# dwm1000_ff3_brd.net
KiCad netlist of a schematic drawn in EAGLE
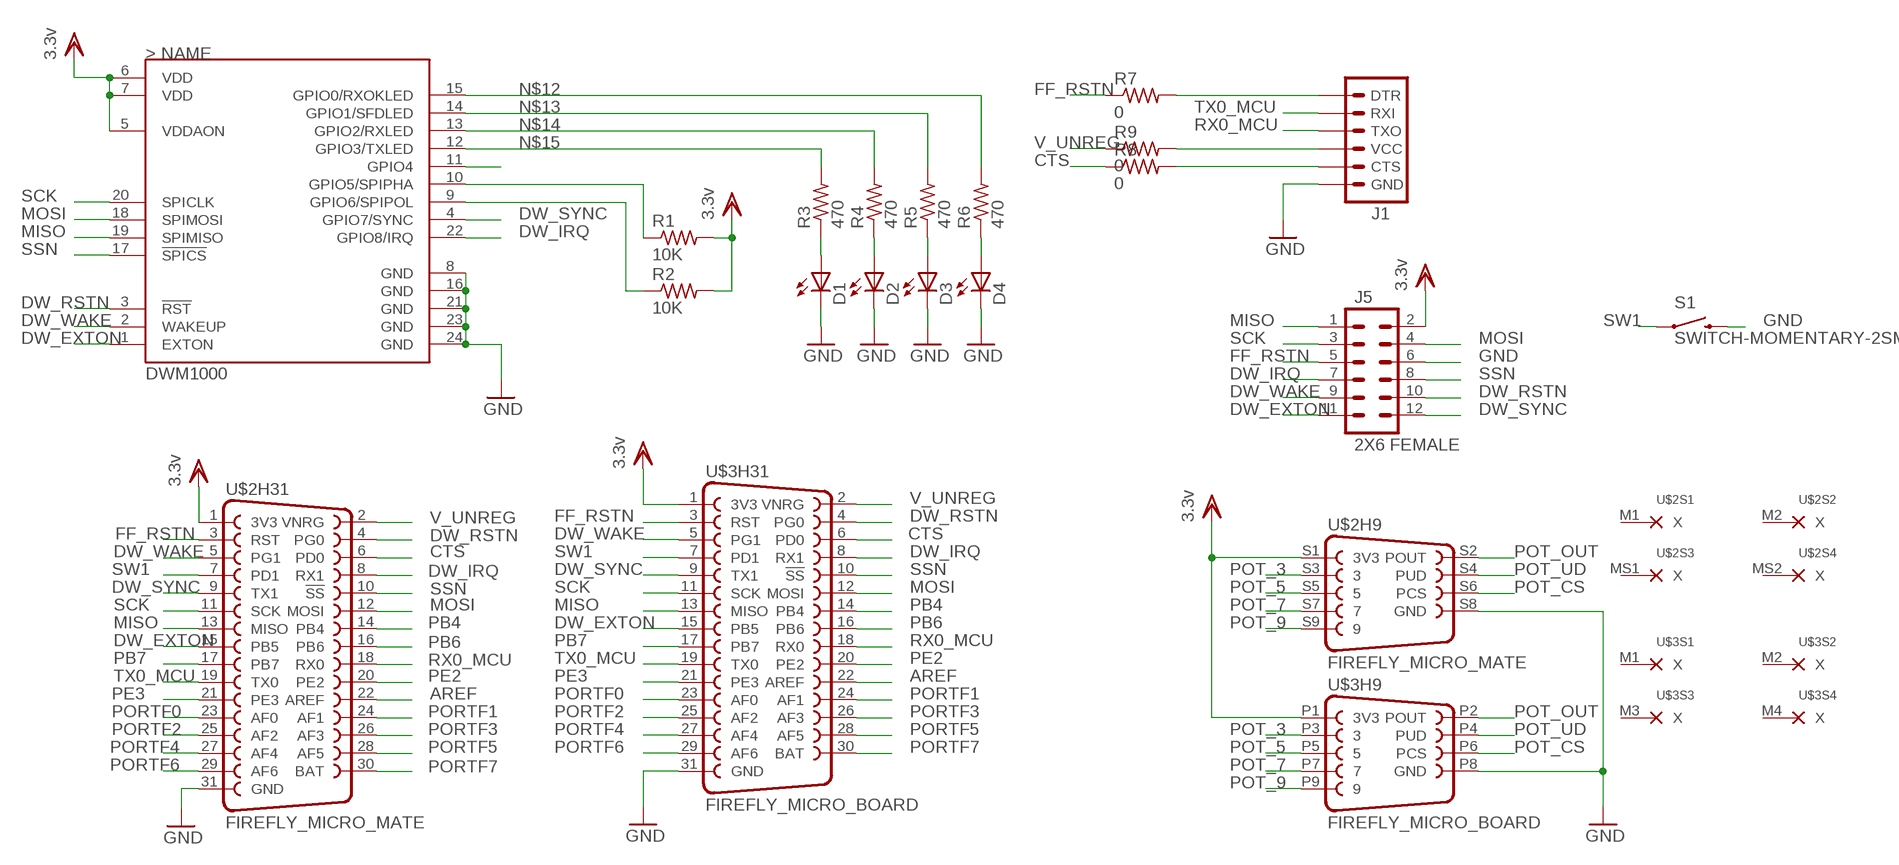
[diagram p0: schematic, sheet 1]

(export (version "E")
  (design (tool "Eeschema 10.0.6"))
  (components
    (comp (ref "D1")
      (value "LEDCHIP-LED0603")
      (footprint "eagle-import:CHIP-LED0603")
      (libsource (lib "eagle-import") (part "LEDCHIP-LED0603"))
    )
    (comp (ref "D2")
      (value "LEDCHIP-LED0603")
      (footprint "eagle-import:CHIP-LED0603")
      (libsource (lib "eagle-import") (part "LEDCHIP-LED0603"))
    )
    (comp (ref "D3")
      (value "LEDCHIP-LED0603")
      (footprint "eagle-import:CHIP-LED0603")
      (libsource (lib "eagle-import") (part "LEDCHIP-LED0603"))
    )
    (comp (ref "D4")
      (value "LEDCHIP-LED0603")
      (footprint "eagle-import:CHIP-LED0603")
      (libsource (lib "eagle-import") (part "LEDCHIP-LED0603"))
    )
    (comp (ref "J1")
      (value "ARDUINO_SERIAL_PROGRAMPTH")
      (footprint "eagle-import:1X06")
      (libsource (lib "eagle-import") (part "ARDUINO_SERIAL_PROGRAMPTH"))
    )
    (comp (ref "J5")
      (value "2X6 FEMALE")
      (footprint "eagle-import:2X6")
      (libsource (lib "eagle-import") (part "M06X2PTH_FEMALE"))
    )
    (comp (ref "R1")
      (value "10K")
      (footprint "eagle-import:R0603")
      (libsource (lib "eagle-import") (part "R-US_R0603"))
    )
    (comp (ref "R2")
      (value "10K")
      (footprint "eagle-import:R0603")
      (libsource (lib "eagle-import") (part "R-US_R0603"))
    )
    (comp (ref "R3")
      (value "470")
      (footprint "eagle-import:R0603")
      (libsource (lib "eagle-import") (part "R-US_R0603"))
    )
    (comp (ref "R4")
      (value "470")
      (footprint "eagle-import:R0603")
      (libsource (lib "eagle-import") (part "R-US_R0603"))
    )
    (comp (ref "R5")
      (value "470")
      (footprint "eagle-import:R0603")
      (libsource (lib "eagle-import") (part "R-US_R0603"))
    )
    (comp (ref "R6")
      (value "470")
      (footprint "eagle-import:R0603")
      (libsource (lib "eagle-import") (part "R-US_R0603"))
    )
    (comp (ref "R7")
      (value "0")
      (footprint "eagle-import:R0603")
      (libsource (lib "eagle-import") (part "R-US_R0603"))
    )
    (comp (ref "R8")
      (value "0")
      (footprint "eagle-import:R0603")
      (libsource (lib "eagle-import") (part "R-US_R0603"))
    )
    (comp (ref "R9")
      (value "0")
      (footprint "eagle-import:R0603")
      (libsource (lib "eagle-import") (part "R-US_R0603"))
    )
    (comp (ref "S1")
      (value "SWITCH-MOMENTARY-2SMD")
      (footprint "eagle-import:TACTILE-SWITCH-SMD")
      (libsource (lib "eagle-import") (part "SWITCH-MOMENTARY-2SMD"))
    )
    (comp (ref "U$1")
      (value "DWM1000")
      (footprint "eagle-import:DWM1000")
      (libsource (lib "eagle-import") (part "DWM1000"))
    )
    (comp (ref "U$2")
      (value "FIREFLY_MICRO_MATE")
      (footprint "eagle-import:FIREFLY_MICRO_MATE")
      (libsource (lib "eagle-import") (part "FIREFLY_MICRO_MATE"))
    )
    (comp (ref "U$3")
      (value "FIREFLY_MICRO_BOARD")
      (footprint "eagle-import:FIREFLY_MICRO_BOARD")
      (libsource (lib "eagle-import") (part "FIREFLY_MICRO_BOARD"))
    )
  )
  (nets
    (net (code "1") (name "/AREF") (class "Default")
      (node (ref "U$2") (pin "22") (pinfunction "AREF_22") (pintype "input"))
      (node (ref "U$3") (pin "22") (pinfunction "AREF_22") (pintype "input"))
    )
    (net (code "2") (name "/CTS") (class "Default")
      (node (ref "R8") (pin "1") (pinfunction "1_1") (pintype "passive"))
      (node (ref "U$2") (pin "6") (pinfunction "PD0_6") (pintype "bidirectional"))
      (node (ref "U$3") (pin "6") (pinfunction "PD0_6") (pintype "bidirectional"))
    )
    (net (code "3") (name "/DW_EXTON") (class "Default")
      (node (ref "J5") (pin "11") (pinfunction "11_11") (pintype "passive"))
      (node (ref "U$1") (pin "1") (pinfunction "EXTON_1") (pintype "input"))
      (node (ref "U$2") (pin "15") (pinfunction "PB5_15") (pintype "bidirectional"))
      (node (ref "U$3") (pin "15") (pinfunction "PB5_15") (pintype "bidirectional"))
    )
    (net (code "4") (name "/DW_IRQ") (class "Default")
      (node (ref "J5") (pin "7") (pinfunction "7_7") (pintype "passive"))
      (node (ref "U$1") (pin "22") (pinfunction "GPIO8/IRQ_22") (pintype "bidirectional"))
      (node (ref "U$2") (pin "8") (pinfunction "RX1_8") (pintype "bidirectional"))
      (node (ref "U$3") (pin "8") (pinfunction "RX1_8") (pintype "bidirectional"))
    )
    (net (code "5") (name "/DW_RSTN") (class "Default")
      (node (ref "J5") (pin "10") (pinfunction "10_10") (pintype "passive"))
      (node (ref "U$1") (pin "3") (pinfunction "~{RST}_3") (pintype "output"))
      (node (ref "U$2") (pin "4") (pinfunction "PG0_4") (pintype "bidirectional"))
      (node (ref "U$3") (pin "4") (pinfunction "PG0_4") (pintype "bidirectional"))
    )
    (net (code "6") (name "/DW_SYNC") (class "Default")
      (node (ref "J5") (pin "12") (pinfunction "12_12") (pintype "passive"))
      (node (ref "U$1") (pin "4") (pinfunction "GPIO7/SYNC_4") (pintype "bidirectional"))
      (node (ref "U$2") (pin "9") (pinfunction "TX1_9") (pintype "bidirectional"))
      (node (ref "U$3") (pin "9") (pinfunction "TX1_9") (pintype "bidirectional"))
    )
    (net (code "7") (name "/DW_WAKE") (class "Default")
      (node (ref "J5") (pin "9") (pinfunction "9_9") (pintype "passive"))
      (node (ref "U$1") (pin "2") (pinfunction "WAKEUP_2") (pintype "input"))
      (node (ref "U$2") (pin "5") (pinfunction "PG1_5") (pintype "bidirectional"))
      (node (ref "U$3") (pin "5") (pinfunction "PG1_5") (pintype "bidirectional"))
    )
    (net (code "8") (name "/FF_RSTN") (class "Default")
      (node (ref "J5") (pin "5") (pinfunction "5_5") (pintype "passive"))
      (node (ref "R7") (pin "1") (pinfunction "1_1") (pintype "passive"))
      (node (ref "U$2") (pin "3") (pinfunction "RST_3") (pintype "input"))
      (node (ref "U$3") (pin "3") (pinfunction "RST_3") (pintype "input"))
    )
    (net (code "9") (name "/MISO") (class "Default")
      (node (ref "J5") (pin "1") (pinfunction "1_1") (pintype "passive"))
      (node (ref "U$1") (pin "19") (pinfunction "SPIMISO_19") (pintype "output"))
      (node (ref "U$2") (pin "13") (pinfunction "MISO_13") (pintype "bidirectional"))
      (node (ref "U$3") (pin "13") (pinfunction "MISO_13") (pintype "bidirectional"))
    )
    (net (code "10") (name "/MOSI") (class "Default")
      (node (ref "J5") (pin "4") (pinfunction "4_4") (pintype "passive"))
      (node (ref "U$1") (pin "18") (pinfunction "SPIMOSI_18") (pintype "input"))
      (node (ref "U$2") (pin "12") (pinfunction "MOSI_12") (pintype "bidirectional"))
      (node (ref "U$3") (pin "12") (pinfunction "MOSI_12") (pintype "bidirectional"))
    )
    (net (code "11") (name "/N$12") (class "Default")
      (node (ref "R6") (pin "2") (pinfunction "2_2") (pintype "passive"))
      (node (ref "U$1") (pin "15") (pinfunction "GPIO0/RXOKLED_15") (pintype "bidirectional"))
    )
    (net (code "12") (name "/N$13") (class "Default")
      (node (ref "R5") (pin "2") (pinfunction "2_2") (pintype "passive"))
      (node (ref "U$1") (pin "14") (pinfunction "GPIO1/SFDLED_14") (pintype "bidirectional"))
    )
    (net (code "13") (name "/N$14") (class "Default")
      (node (ref "R4") (pin "2") (pinfunction "2_2") (pintype "passive"))
      (node (ref "U$1") (pin "13") (pinfunction "GPIO2/RXLED_13") (pintype "bidirectional"))
    )
    (net (code "14") (name "/N$15") (class "Default")
      (node (ref "R3") (pin "2") (pinfunction "2_2") (pintype "passive"))
      (node (ref "U$1") (pin "12") (pinfunction "GPIO3/TXLED_12") (pintype "bidirectional"))
    )
    (net (code "15") (name "/PB4") (class "Default")
      (node (ref "U$2") (pin "14") (pinfunction "PB4_14") (pintype "bidirectional"))
      (node (ref "U$3") (pin "14") (pinfunction "PB4_14") (pintype "bidirectional"))
    )
    (net (code "16") (name "/PB6") (class "Default")
      (node (ref "U$2") (pin "16") (pinfunction "PB6_16") (pintype "bidirectional"))
      (node (ref "U$3") (pin "16") (pinfunction "PB6_16") (pintype "bidirectional"))
    )
    (net (code "17") (name "/PB7") (class "Default")
      (node (ref "U$2") (pin "17") (pinfunction "PB7_17") (pintype "bidirectional"))
      (node (ref "U$3") (pin "17") (pinfunction "PB7_17") (pintype "bidirectional"))
    )
    (net (code "18") (name "/PE2") (class "Default")
      (node (ref "U$2") (pin "20") (pinfunction "PE2_20") (pintype "bidirectional"))
      (node (ref "U$3") (pin "20") (pinfunction "PE2_20") (pintype "bidirectional"))
    )
    (net (code "19") (name "/PE3") (class "Default")
      (node (ref "U$2") (pin "21") (pinfunction "PE3_21") (pintype "bidirectional"))
      (node (ref "U$3") (pin "21") (pinfunction "PE3_21") (pintype "bidirectional"))
    )
    (net (code "20") (name "/PORTF0") (class "Default")
      (node (ref "U$2") (pin "23") (pinfunction "AF0_23") (pintype "bidirectional"))
      (node (ref "U$3") (pin "23") (pinfunction "AF0_23") (pintype "bidirectional"))
    )
    (net (code "21") (name "/PORTF1") (class "Default")
      (node (ref "U$2") (pin "24") (pinfunction "AF1_24") (pintype "bidirectional"))
      (node (ref "U$3") (pin "24") (pinfunction "AF1_24") (pintype "bidirectional"))
    )
    (net (code "22") (name "/PORTF2") (class "Default")
      (node (ref "U$2") (pin "25") (pinfunction "AF2_25") (pintype "bidirectional"))
      (node (ref "U$3") (pin "25") (pinfunction "AF2_25") (pintype "bidirectional"))
    )
    (net (code "23") (name "/PORTF3") (class "Default")
      (node (ref "U$2") (pin "26") (pinfunction "AF3_26") (pintype "bidirectional"))
      (node (ref "U$3") (pin "26") (pinfunction "AF3_26") (pintype "bidirectional"))
    )
    (net (code "24") (name "/PORTF4") (class "Default")
      (node (ref "U$2") (pin "27") (pinfunction "AF4_27") (pintype "bidirectional"))
      (node (ref "U$3") (pin "27") (pinfunction "AF4_27") (pintype "bidirectional"))
    )
    (net (code "25") (name "/PORTF5") (class "Default")
      (node (ref "U$2") (pin "28") (pinfunction "AF5_28") (pintype "bidirectional"))
      (node (ref "U$3") (pin "28") (pinfunction "AF5_28") (pintype "bidirectional"))
    )
    (net (code "26") (name "/PORTF6") (class "Default")
      (node (ref "U$2") (pin "29") (pinfunction "AF6_29") (pintype "bidirectional"))
      (node (ref "U$3") (pin "29") (pinfunction "AF6_29") (pintype "bidirectional"))
    )
    (net (code "27") (name "/PORTF7") (class "Default")
      (node (ref "U$2") (pin "30") (pinfunction "BAT_30") (pintype "bidirectional"))
      (node (ref "U$3") (pin "30") (pinfunction "BAT_30") (pintype "bidirectional"))
    )
    (net (code "28") (name "/POT_3") (class "Default")
      (node (ref "U$2") (pin "S3") (pinfunction "3_S3") (pintype "bidirectional"))
      (node (ref "U$3") (pin "P3") (pinfunction "3_P3") (pintype "bidirectional"))
    )
    (net (code "29") (name "/POT_5") (class "Default")
      (node (ref "U$2") (pin "S5") (pinfunction "5_S5") (pintype "bidirectional"))
      (node (ref "U$3") (pin "P5") (pinfunction "5_P5") (pintype "bidirectional"))
    )
    (net (code "30") (name "/POT_7") (class "Default")
      (node (ref "U$2") (pin "S7") (pinfunction "7_S7") (pintype "bidirectional"))
      (node (ref "U$3") (pin "P7") (pinfunction "7_P7") (pintype "bidirectional"))
    )
    (net (code "31") (name "/POT_9") (class "Default")
      (node (ref "U$2") (pin "S9") (pinfunction "9_S9") (pintype "bidirectional"))
      (node (ref "U$3") (pin "P9") (pinfunction "9_P9") (pintype "bidirectional"))
    )
    (net (code "32") (name "/POT_CS") (class "Default")
      (node (ref "U$2") (pin "S6") (pinfunction "PCS_S6") (pintype "bidirectional"))
      (node (ref "U$3") (pin "P6") (pinfunction "PCS_P6") (pintype "bidirectional"))
    )
    (net (code "33") (name "/POT_OUT") (class "Default")
      (node (ref "U$2") (pin "S2") (pinfunction "POUT_S2") (pintype "bidirectional"))
      (node (ref "U$3") (pin "P2") (pinfunction "POUT_P2") (pintype "bidirectional"))
    )
    (net (code "34") (name "/POT_UD") (class "Default")
      (node (ref "U$2") (pin "S4") (pinfunction "PUD_S4") (pintype "bidirectional"))
      (node (ref "U$3") (pin "P4") (pinfunction "PUD_P4") (pintype "bidirectional"))
    )
    (net (code "35") (name "/RX0_MCU") (class "Default")
      (node (ref "J1") (pin "3") (pinfunction "TXO_3") (pintype "passive"))
      (node (ref "U$2") (pin "18") (pinfunction "RX0_18") (pintype "bidirectional"))
      (node (ref "U$3") (pin "18") (pinfunction "RX0_18") (pintype "bidirectional"))
    )
    (net (code "36") (name "/SCK") (class "Default")
      (node (ref "J5") (pin "3") (pinfunction "3_3") (pintype "passive"))
      (node (ref "U$1") (pin "20") (pinfunction "SPICLK_20") (pintype "output"))
      (node (ref "U$2") (pin "11") (pinfunction "SCK_11") (pintype "bidirectional"))
      (node (ref "U$3") (pin "11") (pinfunction "SCK_11") (pintype "bidirectional"))
    )
    (net (code "37") (name "/SSN") (class "Default")
      (node (ref "J5") (pin "8") (pinfunction "8_8") (pintype "passive"))
      (node (ref "U$1") (pin "17") (pinfunction "~{SPICS}_17") (pintype "input"))
      (node (ref "U$2") (pin "10") (pinfunction "~{SS}_10") (pintype "bidirectional"))
      (node (ref "U$3") (pin "10") (pinfunction "~{SS}_10") (pintype "bidirectional"))
    )
    (net (code "38") (name "/SW1") (class "Default")
      (node (ref "S1") (pin "1") (pinfunction "1_1") (pintype "passive"))
      (node (ref "U$2") (pin "7") (pinfunction "PD1_7") (pintype "bidirectional"))
      (node (ref "U$3") (pin "7") (pinfunction "PD1_7") (pintype "bidirectional"))
    )
    (net (code "39") (name "/TX0_MCU") (class "Default")
      (node (ref "J1") (pin "2") (pinfunction "RXI_2") (pintype "passive"))
      (node (ref "U$2") (pin "19") (pinfunction "TX0_19") (pintype "bidirectional"))
      (node (ref "U$3") (pin "19") (pinfunction "TX0_19") (pintype "bidirectional"))
    )
    (net (code "40") (name "/V_UNREG") (class "Default")
      (node (ref "R9") (pin "1") (pinfunction "1_1") (pintype "passive"))
      (node (ref "U$2") (pin "2") (pinfunction "VNRG_2") (pintype "power_in"))
      (node (ref "U$3") (pin "2") (pinfunction "VNRG_2") (pintype "power_in"))
    )
    (net (code "41") (name "3.3v") (class "Default")
      (node (ref "J5") (pin "2") (pinfunction "2_2") (pintype "passive"))
      (node (ref "R1") (pin "2") (pinfunction "2_2") (pintype "passive"))
      (node (ref "R2") (pin "2") (pinfunction "2_2") (pintype "passive"))
      (node (ref "U$1") (pin "5") (pinfunction "VDDAON_5") (pintype "power_in"))
      (node (ref "U$1") (pin "6") (pinfunction "VDD_6") (pintype "power_in"))
      (node (ref "U$1") (pin "7") (pinfunction "VDD_7") (pintype "power_in"))
      (node (ref "U$2") (pin "1") (pinfunction "3V3_1") (pintype "power_in"))
      (node (ref "U$2") (pin "S1") (pinfunction "3V3_S1") (pintype "power_in"))
      (node (ref "U$3") (pin "1") (pinfunction "3V3_1") (pintype "power_in"))
      (node (ref "U$3") (pin "P1") (pinfunction "3V3_P1") (pintype "power_in"))
    )
    (net (code "42") (name "GND") (class "Default")
      (node (ref "D1") (pin "C") (pinfunction "C_C") (pintype "passive"))
      (node (ref "D2") (pin "C") (pinfunction "C_C") (pintype "passive"))
      (node (ref "D3") (pin "C") (pinfunction "C_C") (pintype "passive"))
      (node (ref "D4") (pin "C") (pinfunction "C_C") (pintype "passive"))
      (node (ref "J1") (pin "6") (pinfunction "GND_6") (pintype "passive"))
      (node (ref "J5") (pin "6") (pinfunction "6_6") (pintype "passive"))
      (node (ref "S1") (pin "3") (pinfunction "2_3") (pintype "passive"))
      (node (ref "U$1") (pin "16") (pinfunction "GND_16") (pintype "power_in"))
      (node (ref "U$1") (pin "21") (pinfunction "GND_21") (pintype "power_in"))
      (node (ref "U$1") (pin "23") (pinfunction "GND_23") (pintype "power_in"))
      (node (ref "U$1") (pin "24") (pinfunction "GND_24") (pintype "power_in"))
      (node (ref "U$1") (pin "8") (pinfunction "GND_8") (pintype "power_in"))
      (node (ref "U$2") (pin "31") (pinfunction "GND_31") (pintype "power_in"))
      (node (ref "U$2") (pin "S8") (pinfunction "GND_S8") (pintype "power_in"))
      (node (ref "U$3") (pin "31") (pinfunction "GND_31") (pintype "power_in"))
      (node (ref "U$3") (pin "P8") (pinfunction "GND_P8") (pintype "power_in"))
    )
    (net (code "43") (name "Net-(D1-PadA)") (class "Default")
      (node (ref "D1") (pin "A") (pinfunction "A_A") (pintype "passive"))
      (node (ref "R3") (pin "1") (pinfunction "1_1") (pintype "passive"))
    )
    (net (code "44") (name "Net-(D2-PadA)") (class "Default")
      (node (ref "D2") (pin "A") (pinfunction "A_A") (pintype "passive"))
      (node (ref "R4") (pin "1") (pinfunction "1_1") (pintype "passive"))
    )
    (net (code "45") (name "Net-(D3-PadA)") (class "Default")
      (node (ref "D3") (pin "A") (pinfunction "A_A") (pintype "passive"))
      (node (ref "R5") (pin "1") (pinfunction "1_1") (pintype "passive"))
    )
    (net (code "46") (name "Net-(D4-PadA)") (class "Default")
      (node (ref "D4") (pin "A") (pinfunction "A_A") (pintype "passive"))
      (node (ref "R6") (pin "1") (pinfunction "1_1") (pintype "passive"))
    )
    (net (code "47") (name "Net-(J1-CTS)") (class "Default")
      (node (ref "J1") (pin "5") (pinfunction "CTS_5") (pintype "passive"))
      (node (ref "R8") (pin "2") (pinfunction "2_2") (pintype "passive"))
    )
    (net (code "48") (name "Net-(J1-DTR)") (class "Default")
      (node (ref "J1") (pin "1") (pinfunction "DTR_1") (pintype "passive"))
      (node (ref "R7") (pin "2") (pinfunction "2_2") (pintype "passive"))
    )
    (net (code "49") (name "Net-(J1-VCC)") (class "Default")
      (node (ref "J1") (pin "4") (pinfunction "VCC_4") (pintype "passive"))
      (node (ref "R9") (pin "2") (pinfunction "2_2") (pintype "passive"))
    )
    (net (code "50") (name "Net-(U$1-GPIO5{slash}SPIPHA)") (class "Default")
      (node (ref "R1") (pin "1") (pinfunction "1_1") (pintype "passive"))
      (node (ref "U$1") (pin "10") (pinfunction "GPIO5/SPIPHA_10") (pintype "bidirectional"))
    )
    (net (code "51") (name "Net-(U$1-GPIO6{slash}SPIPOL)") (class "Default")
      (node (ref "R2") (pin "1") (pinfunction "1_1") (pintype "passive"))
      (node (ref "U$1") (pin "9") (pinfunction "GPIO6/SPIPOL_9") (pintype "bidirectional"))
    )
    (net (code "52") (name "unconnected-(U$1-GPIO4-Pad11)") (class "Default")
      (node (ref "U$1") (pin "11") (pinfunction "GPIO4_11") (pintype "bidirectional"))
    )
    (net (code "53") (name "unconnected-(U$2C-X-PadM1)") (class "Default")
      (node (ref "U$2") (pin "M1") (pinfunction "X_M1") (pintype "no_connect"))
    )
    (net (code "54") (name "unconnected-(U$2D-X-PadM2)") (class "Default")
      (node (ref "U$2") (pin "M2") (pinfunction "X_M2") (pintype "no_connect"))
    )
    (net (code "55") (name "unconnected-(U$2E-X-PadMS1)") (class "Default")
      (node (ref "U$2") (pin "MS1") (pinfunction "X_MS1") (pintype "no_connect"))
    )
    (net (code "56") (name "unconnected-(U$2F-X-PadMS2)") (class "Default")
      (node (ref "U$2") (pin "MS2") (pinfunction "X_MS2") (pintype "no_connect"))
    )
    (net (code "57") (name "unconnected-(U$3C-X-PadM1)") (class "Default")
      (node (ref "U$3") (pin "M1") (pinfunction "X_M1") (pintype "no_connect"))
    )
    (net (code "58") (name "unconnected-(U$3D-X-PadM2)") (class "Default")
      (node (ref "U$3") (pin "M2") (pinfunction "X_M2") (pintype "no_connect"))
    )
    (net (code "59") (name "unconnected-(U$3E-X-PadM3)") (class "Default")
      (node (ref "U$3") (pin "M3") (pinfunction "X_M3") (pintype "no_connect"))
    )
    (net (code "60") (name "unconnected-(U$3F-X-PadM4)") (class "Default")
      (node (ref "U$3") (pin "M4") (pinfunction "X_M4") (pintype "no_connect"))
    )
  )
)
